# uBristleBot.net
KiCad netlist of a schematic drawn in EAGLE
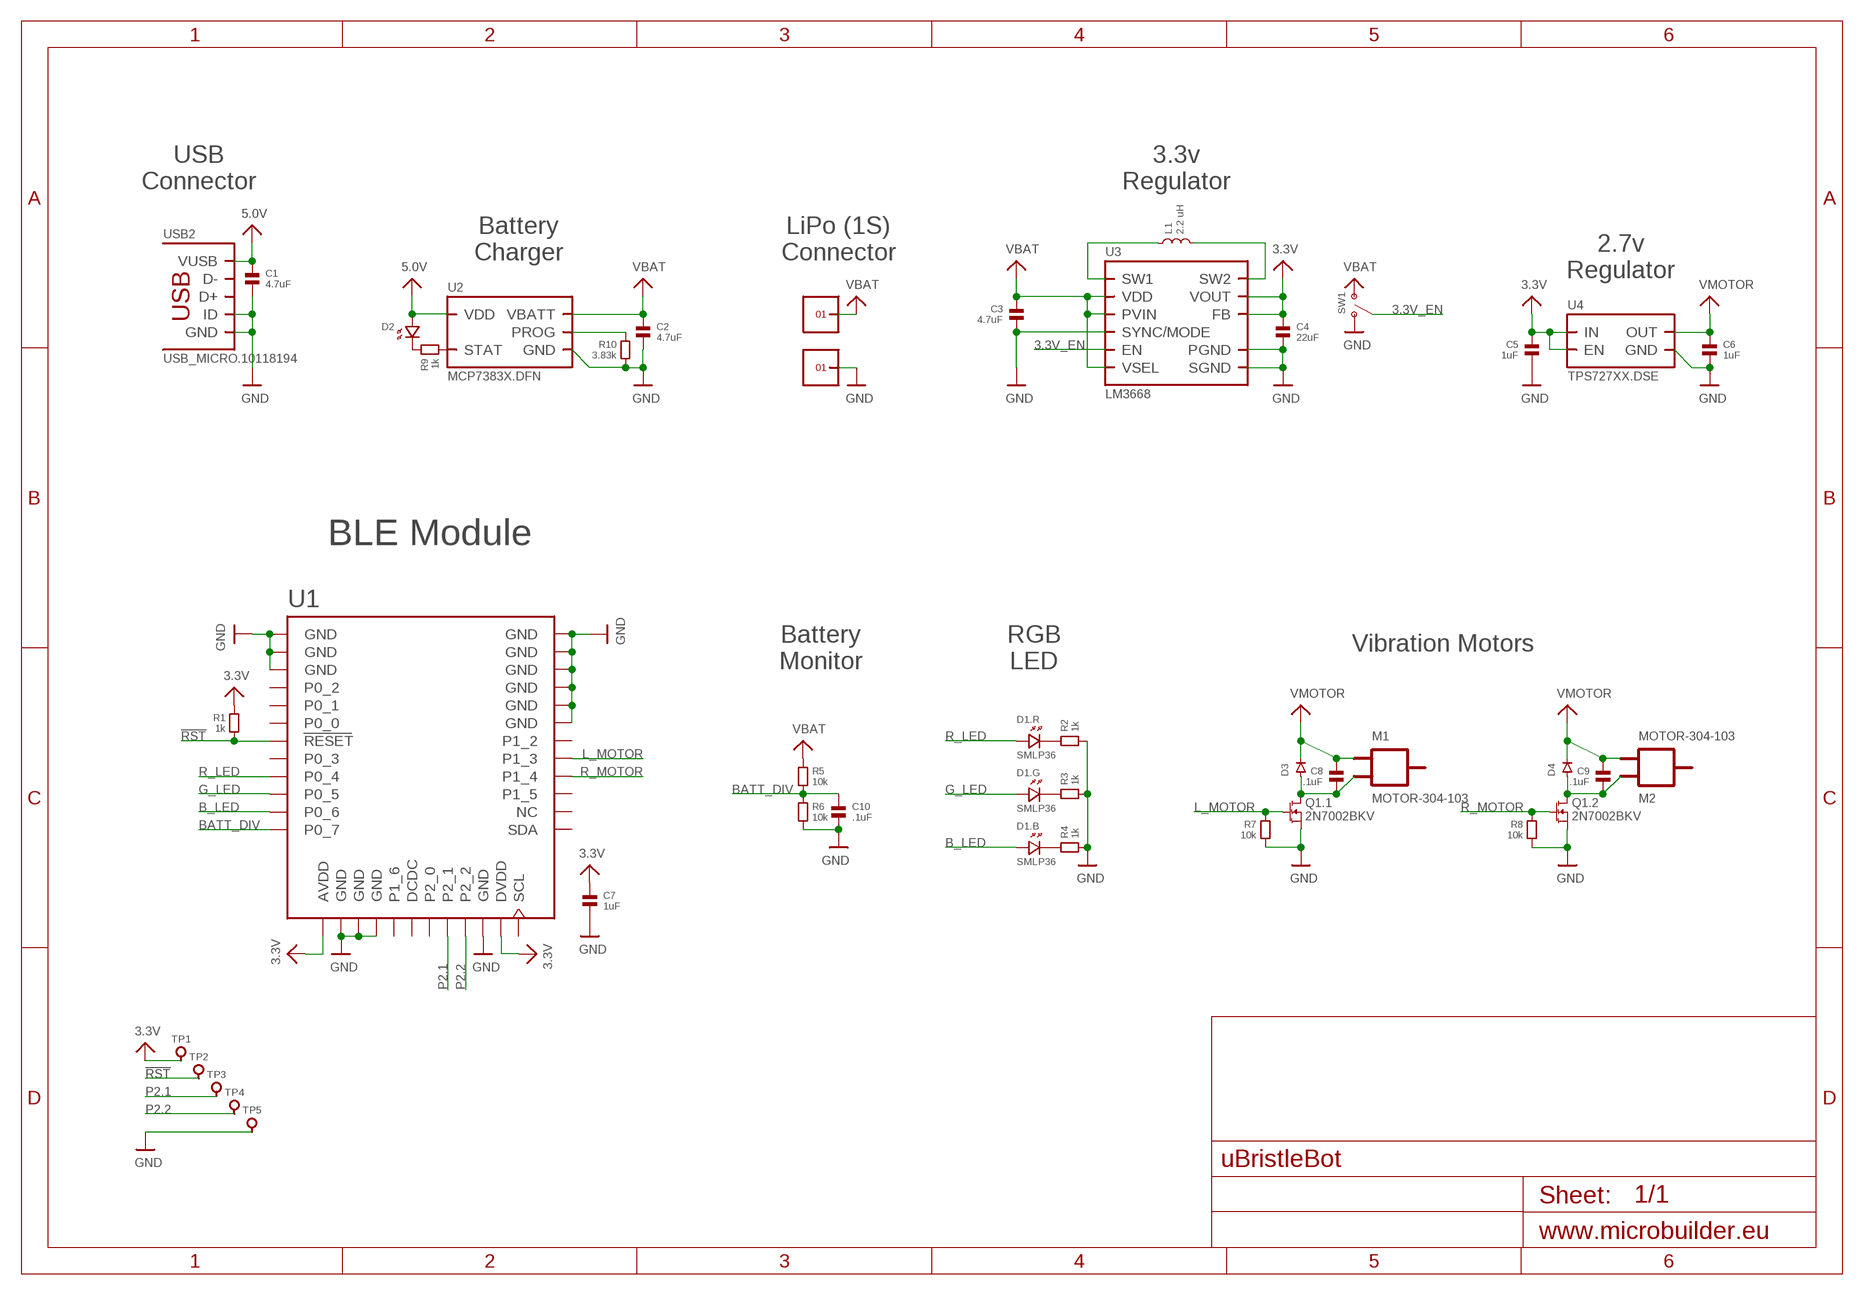
[diagram p0: schematic, sheet 1]

(export (version "E")
  (design (tool "Eeschema 10.0.6"))
  (components
    (comp (ref "C1")
      (value "4.7uF")
      (footprint "eagle-import:0603")
      (libsource (lib "eagle-import") (part "CAPACITOR.0603"))
    )
    (comp (ref "C2")
      (value "4.7uF")
      (footprint "eagle-import:0603")
      (libsource (lib "eagle-import") (part "CAPACITOR.0603"))
    )
    (comp (ref "C3")
      (value "4.7uF")
      (footprint "eagle-import:0603")
      (libsource (lib "eagle-import") (part "CAPACITOR.0603"))
    )
    (comp (ref "C4")
      (value "22uF")
      (footprint "eagle-import:0603")
      (libsource (lib "eagle-import") (part "CAPACITOR.0603"))
    )
    (comp (ref "C5")
      (value "1uF")
      (footprint "eagle-import:0402")
      (libsource (lib "eagle-import") (part "CAPACITOR.0402"))
    )
    (comp (ref "C6")
      (value "1uF")
      (footprint "eagle-import:0402")
      (libsource (lib "eagle-import") (part "CAPACITOR.0402"))
    )
    (comp (ref "C7")
      (value "1uF")
      (footprint "eagle-import:0402")
      (libsource (lib "eagle-import") (part "CAPACITOR.0402"))
    )
    (comp (ref "C8")
      (value ".1uF")
      (footprint "eagle-import:0402")
      (libsource (lib "eagle-import") (part "CAPACITOR.0402"))
    )
    (comp (ref "C9")
      (value ".1uF")
      (footprint "eagle-import:0402")
      (libsource (lib "eagle-import") (part "CAPACITOR.0402"))
    )
    (comp (ref "C10")
      (value ".1uF")
      (footprint "eagle-import:0402")
      (libsource (lib "eagle-import") (part "CAPACITOR.0402"))
    )
    (comp (ref "D1")
      (value "SMLP36")
      (footprint "eagle-import:0604")
      (libsource (lib "eagle-import") (part "SMLP36"))
    )
    (comp (ref "D2")
      (value "LED.0402")
      (footprint "eagle-import:0402.LED")
      (libsource (lib "eagle-import") (part "LED.0402"))
    )
    (comp (ref "D3")
      (value "DIODE.SOD-523F")
      (footprint "eagle-import:SOD-523F")
      (libsource (lib "eagle-import") (part "DIODE.SOD-523F"))
    )
    (comp (ref "D4")
      (value "DIODE.SOD-523F")
      (footprint "eagle-import:SOD-523F")
      (libsource (lib "eagle-import") (part "DIODE.SOD-523F"))
    )
    (comp (ref "L1")
      (value "2.2 uH")
      (footprint "eagle-import:SDR0403")
      (libsource (lib "eagle-import") (part "INDUCTOR-SDR0403"))
    )
    (comp (ref "M1")
      (value "MOTOR-304-103")
      (footprint "eagle-import:304-103")
      (libsource (lib "eagle-import") (part "MOTOR-304-103"))
    )
    (comp (ref "M2")
      (value "MOTOR-304-103")
      (footprint "eagle-import:304-103")
      (libsource (lib "eagle-import") (part "MOTOR-304-103"))
    )
    (comp (ref "Q1")
      (value "2N7002BKV")
      (footprint "eagle-import:SOT666")
      (libsource (lib "eagle-import") (part "2N7002BKV"))
    )
    (comp (ref "R1")
      (value "1k")
      (footprint "eagle-import:0402")
      (libsource (lib "eagle-import") (part "RESISTOR.0402"))
    )
    (comp (ref "R2")
      (value "1k")
      (footprint "eagle-import:0402")
      (libsource (lib "eagle-import") (part "RESISTOR.0402"))
    )
    (comp (ref "R3")
      (value "1k")
      (footprint "eagle-import:0402")
      (libsource (lib "eagle-import") (part "RESISTOR.0402"))
    )
    (comp (ref "R4")
      (value "1k")
      (footprint "eagle-import:0402")
      (libsource (lib "eagle-import") (part "RESISTOR.0402"))
    )
    (comp (ref "R5")
      (value "10k")
      (footprint "eagle-import:0402")
      (libsource (lib "eagle-import") (part "RESISTOR.0402"))
    )
    (comp (ref "R6")
      (value "10k")
      (footprint "eagle-import:0402")
      (libsource (lib "eagle-import") (part "RESISTOR.0402"))
    )
    (comp (ref "R7")
      (value "10k")
      (footprint "eagle-import:0402")
      (libsource (lib "eagle-import") (part "RESISTOR.0402"))
    )
    (comp (ref "R8")
      (value "10k")
      (footprint "eagle-import:0402")
      (libsource (lib "eagle-import") (part "RESISTOR.0402"))
    )
    (comp (ref "R9")
      (value "1k")
      (footprint "eagle-import:0402")
      (libsource (lib "eagle-import") (part "RESISTOR.0402"))
    )
    (comp (ref "R10")
      (value "3.83k")
      (footprint "eagle-import:0402")
      (libsource (lib "eagle-import") (part "RESISTOR.0402"))
    )
    (comp (ref "SW1")
      (value "SSAJ110100")
      (footprint "eagle-import:SSAJ110100")
      (libsource (lib "eagle-import") (part "SSAJ110100"))
    )
    (comp (ref "TP1")
      (value "PCB_PAD.42MIL")
      (footprint "eagle-import:0906-0_PAD")
      (libsource (lib "eagle-import") (part "PCB_PAD.42MIL"))
    )
    (comp (ref "TP2")
      (value "PCB_PAD.42MIL")
      (footprint "eagle-import:0906-0_PAD")
      (libsource (lib "eagle-import") (part "PCB_PAD.42MIL"))
    )
    (comp (ref "TP3")
      (value "PCB_PAD.42MIL")
      (footprint "eagle-import:0906-0_PAD")
      (libsource (lib "eagle-import") (part "PCB_PAD.42MIL"))
    )
    (comp (ref "TP4")
      (value "PCB_PAD.42MIL")
      (footprint "eagle-import:0906-0_PAD")
      (libsource (lib "eagle-import") (part "PCB_PAD.42MIL"))
    )
    (comp (ref "TP5")
      (value "PCB_PAD.42MIL")
      (footprint "eagle-import:0906-0_PAD")
      (libsource (lib "eagle-import") (part "PCB_PAD.42MIL"))
    )
    (comp (ref "U$31")
      (value "1X1")
      (footprint "eagle-import:1X1")
      (libsource (lib "eagle-import") (part "1X1"))
    )
    (comp (ref "U$34")
      (value "1X1")
      (footprint "eagle-import:1X1")
      (libsource (lib "eagle-import") (part "1X1"))
    )
    (comp (ref "U1")
      (value "BLE121LR-VISUAL-A")
      (footprint "eagle-import:BLE121LR-A")
      (libsource (lib "eagle-import") (part "BLE121LR-VISUAL-A"))
    )
    (comp (ref "U2")
      (value "MCP7383X.DFN")
      (footprint "eagle-import:DFN8-3X2.PAD")
      (libsource (lib "eagle-import") (part "MCP7383X.DFN"))
    )
    (comp (ref "U3")
      (value "LM3668")
      (footprint "eagle-import:LLP.12.3X3MM")
      (libsource (lib "eagle-import") (part "LM3668"))
    )
    (comp (ref "U4")
      (value "TPS727XX.DSE")
      (footprint "eagle-import:DSE")
      (libsource (lib "eagle-import") (part "TPS727XX.DSE"))
    )
    (comp (ref "USB2")
      (value "USB_MICRO.10118194")
      (footprint "eagle-import:10118194")
      (libsource (lib "eagle-import") (part "USB_MICRO.10118194"))
    )
  )
  (nets
    (net (code "1") (name "/3.3V_EN") (class "Default")
      (node (ref "SW1") (pin "C") (pinfunction "COM_C") (pintype "bidirectional"))
      (node (ref "U3") (pin "6") (pinfunction "EN_6") (pintype "bidirectional"))
    )
    (net (code "2") (name "/BATT_DIV") (class "Default")
      (node (ref "C10") (pin "1") (pinfunction "1_1") (pintype "bidirectional"))
      (node (ref "R5") (pin "2") (pinfunction "2_2") (pintype "bidirectional"))
      (node (ref "R6") (pin "1") (pinfunction "1_1") (pintype "bidirectional"))
      (node (ref "U1") (pin "P0_7") (pinfunction "P0_7_P0_7") (pintype "bidirectional"))
    )
    (net (code "3") (name "/B_LED") (class "Default")
      (node (ref "D1") (pin "1") (pinfunction "+_1") (pintype "bidirectional"))
      (node (ref "U1") (pin "P0_6") (pinfunction "P0_6_P0_6") (pintype "bidirectional"))
    )
    (net (code "4") (name "/G_LED") (class "Default")
      (node (ref "D1") (pin "3") (pinfunction "+_3") (pintype "bidirectional"))
      (node (ref "U1") (pin "P0_5") (pinfunction "P0_5_P0_5") (pintype "bidirectional"))
    )
    (net (code "5") (name "/L_MOTOR") (class "Default")
      (node (ref "Q1") (pin "2") (pinfunction "G_2") (pintype "bidirectional"))
      (node (ref "R7") (pin "1") (pinfunction "1_1") (pintype "bidirectional"))
      (node (ref "U1") (pin "P1_3") (pinfunction "P1_3_P1_3") (pintype "bidirectional"))
    )
    (net (code "6") (name "/P2.1") (class "Default")
      (node (ref "TP3") (pin "PAD") (pinfunction "PIN_PAD") (pintype "bidirectional"))
      (node (ref "U1") (pin "P2_1") (pinfunction "P2_1_P2_1") (pintype "bidirectional"))
    )
    (net (code "7") (name "/P2.2") (class "Default")
      (node (ref "TP4") (pin "PAD") (pinfunction "PIN_PAD") (pintype "bidirectional"))
      (node (ref "U1") (pin "P2_2") (pinfunction "P2_2_P2_2") (pintype "bidirectional"))
    )
    (net (code "8") (name "/R_LED") (class "Default")
      (node (ref "D1") (pin "2") (pinfunction "+_2") (pintype "bidirectional"))
      (node (ref "U1") (pin "P0_4") (pinfunction "P0_4_P0_4") (pintype "bidirectional"))
    )
    (net (code "9") (name "/R_MOTOR") (class "Default")
      (node (ref "Q1") (pin "5") (pinfunction "G_5") (pintype "bidirectional"))
      (node (ref "R8") (pin "1") (pinfunction "1_1") (pintype "bidirectional"))
      (node (ref "U1") (pin "P1_4") (pinfunction "P1_4_P1_4") (pintype "bidirectional"))
    )
    (net (code "10") (name "/~{RST}") (class "Default")
      (node (ref "R1") (pin "2") (pinfunction "2_2") (pintype "bidirectional"))
      (node (ref "TP2") (pin "PAD") (pinfunction "PIN_PAD") (pintype "bidirectional"))
      (node (ref "U1") (pin "RESET") (pinfunction "RESET_RESET") (pintype "input"))
    )
    (net (code "11") (name "3.3V") (class "Default")
      (node (ref "C4") (pin "1") (pinfunction "1_1") (pintype "bidirectional"))
      (node (ref "C5") (pin "1") (pinfunction "1_1") (pintype "bidirectional"))
      (node (ref "C7") (pin "1") (pinfunction "1_1") (pintype "bidirectional"))
      (node (ref "R1") (pin "1") (pinfunction "1_1") (pintype "bidirectional"))
      (node (ref "TP1") (pin "PAD") (pinfunction "PIN_PAD") (pintype "bidirectional"))
      (node (ref "U1") (pin "AVDD") (pinfunction "AVDD_AVDD") (pintype "power_in"))
      (node (ref "U1") (pin "DVDD") (pinfunction "DVDD_DVDD") (pintype "power_in"))
      (node (ref "U3") (pin "1") (pinfunction "VOUT_1") (pintype "bidirectional"))
      (node (ref "U3") (pin "12") (pinfunction "FB_12") (pintype "bidirectional"))
      (node (ref "U4") (pin "4") (pinfunction "EN_4") (pintype "bidirectional"))
      (node (ref "U4") (pin "6") (pinfunction "IN_6") (pintype "bidirectional"))
    )
    (net (code "12") (name "5.0V") (class "Default")
      (node (ref "C1") (pin "1") (pinfunction "1_1") (pintype "bidirectional"))
      (node (ref "D2") (pin "P$1") (pinfunction "1_P$1") (pintype "bidirectional"))
      (node (ref "U2") (pin "1") (pinfunction "VDD_1") (pintype "bidirectional"))
      (node (ref "U2") (pin "2") (pinfunction "VDD_2") (pintype "bidirectional"))
      (node (ref "USB2") (pin "1") (pinfunction "VUSB_1") (pintype "bidirectional"))
    )
    (net (code "13") (name "GND") (class "Default")
      (node (ref "C1") (pin "2") (pinfunction "2_2") (pintype "bidirectional"))
      (node (ref "C10") (pin "2") (pinfunction "2_2") (pintype "bidirectional"))
      (node (ref "C2") (pin "2") (pinfunction "2_2") (pintype "bidirectional"))
      (node (ref "C3") (pin "2") (pinfunction "2_2") (pintype "bidirectional"))
      (node (ref "C4") (pin "2") (pinfunction "2_2") (pintype "bidirectional"))
      (node (ref "C5") (pin "2") (pinfunction "2_2") (pintype "bidirectional"))
      (node (ref "C6") (pin "2") (pinfunction "2_2") (pintype "bidirectional"))
      (node (ref "C7") (pin "2") (pinfunction "2_2") (pintype "bidirectional"))
      (node (ref "Q1") (pin "1") (pinfunction "S_1") (pintype "bidirectional"))
      (node (ref "Q1") (pin "4") (pinfunction "S_4") (pintype "bidirectional"))
      (node (ref "R10") (pin "2") (pinfunction "2_2") (pintype "bidirectional"))
      (node (ref "R2") (pin "2") (pinfunction "2_2") (pintype "bidirectional"))
      (node (ref "R3") (pin "2") (pinfunction "2_2") (pintype "bidirectional"))
      (node (ref "R4") (pin "2") (pinfunction "2_2") (pintype "bidirectional"))
      (node (ref "R6") (pin "2") (pinfunction "2_2") (pintype "bidirectional"))
      (node (ref "R7") (pin "2") (pinfunction "2_2") (pintype "bidirectional"))
      (node (ref "R8") (pin "2") (pinfunction "2_2") (pintype "bidirectional"))
      (node (ref "SW1") (pin "1") (pinfunction "A_1") (pintype "bidirectional"))
      (node (ref "TP5") (pin "PAD") (pinfunction "PIN_PAD") (pintype "bidirectional"))
      (node (ref "U$34") (pin "1") (pinfunction "1_1") (pintype "bidirectional"))
      (node (ref "U1") (pin "GND") (pinfunction "GND_GND") (pintype "power_in"))
      (node (ref "U1") (pin "GND@10") (pinfunction "GND_GND@10") (pintype "power_in"))
      (node (ref "U1") (pin "GND@11") (pinfunction "GND_GND@11") (pintype "power_in"))
      (node (ref "U1") (pin "GND@12") (pinfunction "GND_GND@12") (pintype "power_in"))
      (node (ref "U1") (pin "GND@13") (pinfunction "GND_GND@13") (pintype "power_in"))
      (node (ref "U1") (pin "GND@2") (pinfunction "GND_GND@2") (pintype "power_in"))
      (node (ref "U1") (pin "GND@3") (pinfunction "GND_GND@3") (pintype "power_in"))
      (node (ref "U1") (pin "GND@4") (pinfunction "GND_GND@4") (pintype "power_in"))
      (node (ref "U1") (pin "GND@5") (pinfunction "GND_GND@5") (pintype "power_in"))
      (node (ref "U1") (pin "GND@6") (pinfunction "GND_GND@6") (pintype "power_in"))
      (node (ref "U1") (pin "GND@7") (pinfunction "GND_GND@7") (pintype "power_in"))
      (node (ref "U1") (pin "GND@8") (pinfunction "GND_GND@8") (pintype "power_in"))
      (node (ref "U1") (pin "GND@9") (pinfunction "GND_GND@9") (pintype "power_in"))
      (node (ref "U2") (pin "6") (pinfunction "GND_6") (pintype "bidirectional"))
      (node (ref "U2") (pin "PAD") (pinfunction "GND_PAD") (pintype "bidirectional"))
      (node (ref "U3") (pin "10") (pinfunction "SYNC/MODE_10") (pintype "bidirectional"))
      (node (ref "U3") (pin "3") (pinfunction "PGND_3") (pintype "bidirectional"))
      (node (ref "U3") (pin "8") (pinfunction "SGND_8") (pintype "bidirectional"))
      (node (ref "U3") (pin "9") (pinfunction "SGND_9") (pintype "bidirectional"))
      (node (ref "U3") (pin "PAD") (pinfunction "SGND_PAD") (pintype "bidirectional"))
      (node (ref "U4") (pin "3") (pinfunction "GND_3") (pintype "bidirectional"))
      (node (ref "USB2") (pin "4") (pinfunction "ID_4") (pintype "bidirectional"))
      (node (ref "USB2") (pin "5") (pinfunction "GND_5") (pintype "bidirectional"))
      (node (ref "USB2") (pin "PAD@1") (pinfunction "GND_PAD@1") (pintype "bidirectional"))
      (node (ref "USB2") (pin "PAD@10") (pinfunction "GND_PAD@10") (pintype "bidirectional"))
      (node (ref "USB2") (pin "PAD@11") (pinfunction "GND_PAD@11") (pintype "bidirectional"))
      (node (ref "USB2") (pin "PAD@12") (pinfunction "GND_PAD@12") (pintype "bidirectional"))
      (node (ref "USB2") (pin "PAD@13") (pinfunction "GND_PAD@13") (pintype "bidirectional"))
      (node (ref "USB2") (pin "PAD@14") (pinfunction "GND_PAD@14") (pintype "bidirectional"))
      (node (ref "USB2") (pin "PAD@15") (pinfunction "GND_PAD@15") (pintype "bidirectional"))
      (node (ref "USB2") (pin "PAD@16") (pinfunction "GND_PAD@16") (pintype "bidirectional"))
      (node (ref "USB2") (pin "PAD@2") (pinfunction "GND_PAD@2") (pintype "bidirectional"))
      (node (ref "USB2") (pin "PAD@3") (pinfunction "GND_PAD@3") (pintype "bidirectional"))
      (node (ref "USB2") (pin "PAD@4") (pinfunction "GND_PAD@4") (pintype "bidirectional"))
      (node (ref "USB2") (pin "PAD@5") (pinfunction "GND_PAD@5") (pintype "bidirectional"))
      (node (ref "USB2") (pin "PAD@6") (pinfunction "GND_PAD@6") (pintype "bidirectional"))
      (node (ref "USB2") (pin "PAD@7") (pinfunction "GND_PAD@7") (pintype "bidirectional"))
      (node (ref "USB2") (pin "PAD@8") (pinfunction "GND_PAD@8") (pintype "bidirectional"))
      (node (ref "USB2") (pin "PAD@9") (pinfunction "GND_PAD@9") (pintype "bidirectional"))
    )
    (net (code "14") (name "Net-(D1A--)") (class "Default")
      (node (ref "D1") (pin "6") (pinfunction "-_6") (pintype "bidirectional"))
      (node (ref "R4") (pin "1") (pinfunction "1_1") (pintype "bidirectional"))
    )
    (net (code "15") (name "Net-(D1B--)") (class "Default")
      (node (ref "D1") (pin "4") (pinfunction "-_4") (pintype "bidirectional"))
      (node (ref "R3") (pin "1") (pinfunction "1_1") (pintype "bidirectional"))
    )
    (net (code "16") (name "Net-(D1C--)") (class "Default")
      (node (ref "D1") (pin "5") (pinfunction "-_5") (pintype "bidirectional"))
      (node (ref "R2") (pin "1") (pinfunction "1_1") (pintype "bidirectional"))
    )
    (net (code "17") (name "Net-(D2-2)") (class "Default")
      (node (ref "D2") (pin "P$2") (pinfunction "2_P$2") (pintype "bidirectional"))
      (node (ref "R9") (pin "1") (pinfunction "1_1") (pintype "bidirectional"))
    )
    (net (code "18") (name "Net-(Q1A-D)") (class "Default")
      (node (ref "C8") (pin "2") (pinfunction "2_2") (pintype "bidirectional"))
      (node (ref "D3") (pin "A") (pinfunction "A_A") (pintype "bidirectional"))
      (node (ref "M1") (pin "2") (pinfunction "2_2") (pintype "bidirectional"))
      (node (ref "Q1") (pin "6") (pinfunction "D_6") (pintype "bidirectional"))
    )
    (net (code "19") (name "Net-(Q1B-D)") (class "Default")
      (node (ref "C9") (pin "2") (pinfunction "2_2") (pintype "bidirectional"))
      (node (ref "D4") (pin "A") (pinfunction "A_A") (pintype "bidirectional"))
      (node (ref "M2") (pin "1") (pinfunction "1_1") (pintype "bidirectional"))
      (node (ref "Q1") (pin "3") (pinfunction "D_3") (pintype "bidirectional"))
    )
    (net (code "20") (name "Net-(U2-PROG)") (class "Default")
      (node (ref "R10") (pin "1") (pinfunction "1_1") (pintype "bidirectional"))
      (node (ref "U2") (pin "8") (pinfunction "PROG_8") (pintype "bidirectional"))
    )
    (net (code "21") (name "Net-(U2-STAT)") (class "Default")
      (node (ref "R9") (pin "2") (pinfunction "2_2") (pintype "bidirectional"))
      (node (ref "U2") (pin "5") (pinfunction "STAT_5") (pintype "bidirectional"))
    )
    (net (code "22") (name "Net-(U3-SW1)") (class "Default")
      (node (ref "L1") (pin "1") (pinfunction "1_1") (pintype "passive"))
      (node (ref "U3") (pin "4") (pinfunction "SW1_4") (pintype "bidirectional"))
    )
    (net (code "23") (name "Net-(U3-SW2)") (class "Default")
      (node (ref "L1") (pin "2") (pinfunction "2_2") (pintype "passive"))
      (node (ref "U3") (pin "2") (pinfunction "SW2_2") (pintype "bidirectional"))
    )
    (net (code "24") (name "VBAT") (class "Default")
      (node (ref "C2") (pin "1") (pinfunction "1_1") (pintype "bidirectional"))
      (node (ref "C3") (pin "1") (pinfunction "1_1") (pintype "bidirectional"))
      (node (ref "R5") (pin "1") (pinfunction "1_1") (pintype "bidirectional"))
      (node (ref "SW1") (pin "2") (pinfunction "B_2") (pintype "bidirectional"))
      (node (ref "U$31") (pin "1") (pinfunction "1_1") (pintype "bidirectional"))
      (node (ref "U2") (pin "3") (pinfunction "VBATT_3") (pintype "bidirectional"))
      (node (ref "U2") (pin "4") (pinfunction "VBATT_4") (pintype "bidirectional"))
      (node (ref "U3") (pin "11") (pinfunction "VSEL_11") (pintype "bidirectional"))
      (node (ref "U3") (pin "5") (pinfunction "PVIN_5") (pintype "bidirectional"))
      (node (ref "U3") (pin "7") (pinfunction "VDD_7") (pintype "bidirectional"))
    )
    (net (code "25") (name "VMOTOR") (class "Default")
      (node (ref "C6") (pin "1") (pinfunction "1_1") (pintype "bidirectional"))
      (node (ref "C8") (pin "1") (pinfunction "1_1") (pintype "bidirectional"))
      (node (ref "C9") (pin "1") (pinfunction "1_1") (pintype "bidirectional"))
      (node (ref "D3") (pin "C") (pinfunction "C_C") (pintype "bidirectional"))
      (node (ref "D4") (pin "C") (pinfunction "C_C") (pintype "bidirectional"))
      (node (ref "M1") (pin "1") (pinfunction "1_1") (pintype "bidirectional"))
      (node (ref "M2") (pin "2") (pinfunction "2_2") (pintype "bidirectional"))
      (node (ref "U4") (pin "1") (pinfunction "OUT_1") (pintype "bidirectional"))
    )
    (net (code "26") (name "unconnected-(U1-PadDCDC)") (class "Default")
      (node (ref "U1") (pin "DCDC") (pinfunction "DCDC_DCDC") (pintype "bidirectional"))
    )
    (net (code "27") (name "unconnected-(U1-PadNC)") (class "Default")
      (node (ref "U1") (pin "NC") (pinfunction "NC_NC") (pintype "no_connect"))
    )
    (net (code "28") (name "unconnected-(U1-PadP0_0)") (class "Default")
      (node (ref "U1") (pin "P0_0") (pinfunction "P0_0_P0_0") (pintype "bidirectional"))
    )
    (net (code "29") (name "unconnected-(U1-PadP0_1)") (class "Default")
      (node (ref "U1") (pin "P0_1") (pinfunction "P0_1_P0_1") (pintype "bidirectional"))
    )
    (net (code "30") (name "unconnected-(U1-PadP0_2)") (class "Default")
      (node (ref "U1") (pin "P0_2") (pinfunction "P0_2_P0_2") (pintype "bidirectional"))
    )
    (net (code "31") (name "unconnected-(U1-PadP0_3)") (class "Default")
      (node (ref "U1") (pin "P0_3") (pinfunction "P0_3_P0_3") (pintype "bidirectional"))
    )
    (net (code "32") (name "unconnected-(U1-PadP1_2)") (class "Default")
      (node (ref "U1") (pin "P1_2") (pinfunction "P1_2_P1_2") (pintype "bidirectional"))
    )
    (net (code "33") (name "unconnected-(U1-PadP1_5)") (class "Default")
      (node (ref "U1") (pin "P1_5") (pinfunction "P1_5_P1_5") (pintype "bidirectional"))
    )
    (net (code "34") (name "unconnected-(U1-PadP1_6)") (class "Default")
      (node (ref "U1") (pin "P1_6") (pinfunction "P1_6_P1_6") (pintype "bidirectional"))
    )
    (net (code "35") (name "unconnected-(U1-PadP2_0)") (class "Default")
      (node (ref "U1") (pin "P2_0") (pinfunction "P2_0_P2_0") (pintype "bidirectional"))
    )
    (net (code "36") (name "unconnected-(U1-PadSCL)") (class "Default")
      (node (ref "U1") (pin "SCL") (pinfunction "SCL_SCL") (pintype "bidirectional"))
    )
    (net (code "37") (name "unconnected-(U1-PadSDA)") (class "Default")
      (node (ref "U1") (pin "SDA") (pinfunction "SDA_SDA") (pintype "bidirectional"))
    )
    (net (code "38") (name "unconnected-(USB2-D+-Pad3)") (class "Default")
      (node (ref "USB2") (pin "3") (pinfunction "D+_3") (pintype "bidirectional"))
    )
    (net (code "39") (name "unconnected-(USB2-D--Pad2)") (class "Default")
      (node (ref "USB2") (pin "2") (pinfunction "D-_2") (pintype "bidirectional"))
    )
  )
)
